# MCU.net
KiCad netlist of a schematic drawn in Altium Designer
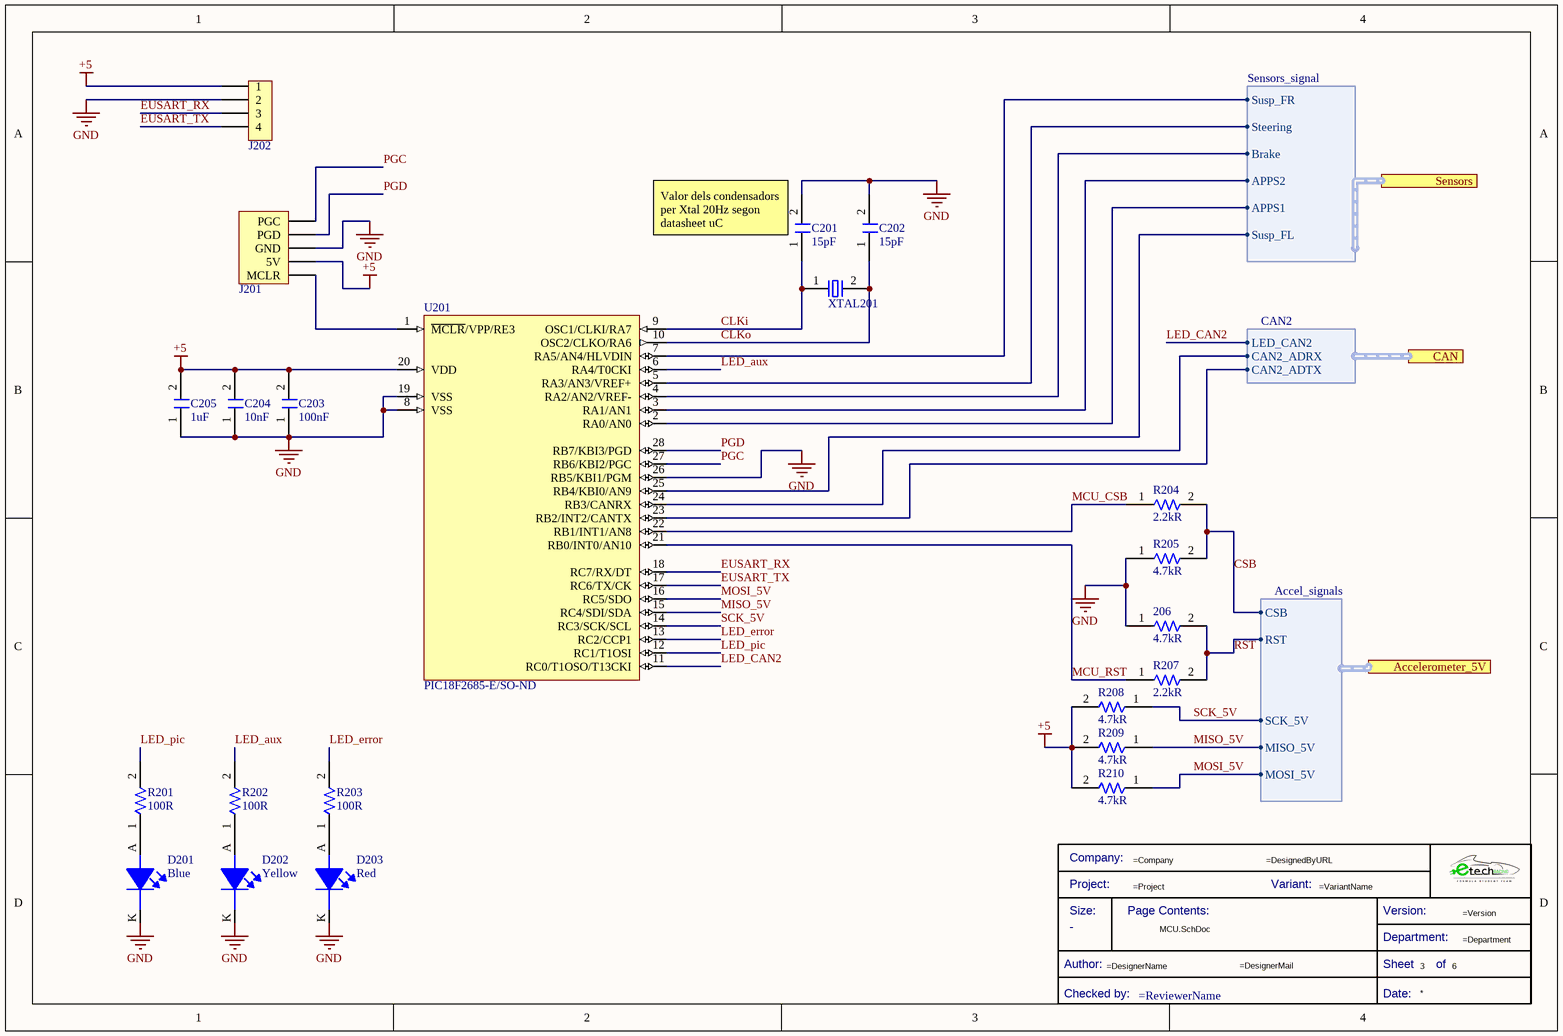
[diagram p0: MCU.SchDoc]

(export (version "E")
  (design (tool "Eeschema 10.0.6"))
  (components
    (comp (ref "*")
      (value "Title Block_template")
      (description "Standard Title Block")
      (fields
        (field (name "SIZE") "-")
        (field (name ".CREATOR") "GP")
        (field (name ".PCBCHECK") "GP")
        (field (name ".SCHCHECK") "GP")
      )
      (libsource (lib "e-Tech_Racing") (part "Title Block_template"))
    )
    (comp (ref "206")
      (value "CRS1206-FX-4701ELF")
      (footprint "R1206FTK-W")
      (description "Res Thick Film 1206 4.7K Ohm 1% 1/2W ±100ppm/°C Molded SMD T/R")
      (fields (field (name "TOLERANCE") "1%") (field (name "RESISTANCE") "4.7kR"))
      (libsource (lib "Passives") (part "R4.7K-1206FTK"))
    )
    (comp (ref "C201")
      (value "885012008038")
      (footprint "C1206FNPC-RW")
      (description "Cap, 15Pf, 50V, 5%, C0G/np0, 1206 Rohs Compliant: Yes")
      (fields
        (field (name "MANUFACTURER") "Wurth Electronics")
        (field (name "TOLERANCE") "5%")
        (field (name "CAPACITANCE") "15pF")
      )
      (libsource (lib "Passives") (part "C15p-50V-1206FNPC-NP0"))
    )
    (comp (ref "C202")
      (value "885012008038")
      (footprint "C1206FNPC-RW")
      (description "Cap, 15Pf, 50V, 5%, C0G/np0, 1206 Rohs Compliant: Yes")
      (fields
        (field (name "MANUFACTURER") "Wurth Electronics")
        (field (name "TOLERANCE") "5%")
        (field (name "CAPACITANCE") "15pF")
      )
      (libsource (lib "Passives") (part "C15p-50V-1206FNPC-NP0"))
    )
    (comp (ref "C203")
      (value "885012208009")
      (footprint "C1206FNPC-RW")
      (description "Cap, 0.1ΜF, 10V, 10%, X7R, 1206")
      (fields (field (name "TOLERANCE") "10%") (field (name "CAPACITANCE") "100nF"))
      (libsource (lib "Passives") (part "C100n-10V-1206FNPC-X7R"))
    )
    (comp (ref "C204")
      (value "885012208009")
      (footprint "C1206FNPC-RW")
      (description "Cap, 0.1ΜF, 10V, 10%, X7R, 1206")
      (fields (field (name "TOLERANCE") "10%") (field (name "CAPACITANCE") "10nF"))
      (libsource (lib "Passives") (part "C100n-10V-1206FNPC-X7R"))
    )
    (comp (ref "C205")
      (value "885012208009")
      (footprint "C1206FNPC-RW")
      (description "Cap, 0.1ΜF, 10V, 10%, X7R, 1206")
      (fields (field (name "TOLERANCE") "10%") (field (name "CAPACITANCE") "1uF"))
      (libsource (lib "Passives") (part "C100n-10V-1206FNPC-X7R"))
    )
    (comp (ref "D201")
      (value "150120BS75000")
      (footprint "LED_1206_WE")
      (description "Led, Blue, 470 Nm, 3.2 V, 30 Ma, 145 Mcd Rohs Compliant: Yes")
      (fields (field (name "MANUFACTURER") "Wurth Electronics") (field (name "COLOR") "Blue"))
      (libsource (lib "Semiconductor") (part "LEDBS-1206-145"))
    )
    (comp (ref "D202")
      (value "150120YS75000")
      (footprint "LED_1206_WE")
      (description "Led, Yellow, 590 Nm, 2 V, 30 Ma, 120 Mcd Rohs Compliant: Yes")
      (fields (field (name "MANUFACTURER") "Wurth Electronics") (field (name "COLOR") "Yellow"))
      (libsource (lib "Semiconductor") (part "LEDYS-1206-120"))
    )
    (comp (ref "D203")
      (value "150120RS75000")
      (footprint "LED_1206_WE")
      (description "Led, Red, 625 Nm, 2 V, 30 Ma, 150 Mcd Rohs Compliant: Yes")
      (fields (field (name "MANUFACTURER") "Wurth Electronics") (field (name "COLOR") "Red"))
      (libsource (lib "Semiconductor") (part "LEDRS-1206-150"))
    )
    (comp (ref "J201")
      (value "61300511121")
      (footprint "J_Bootloader_PIC")
      (description "THT Vertical Pin Header WR-PHD, Pitch 2.54 mm, Single Row, 5 pins")
      (fields (field (name "MANUFACTURER") "Molex"))
      (libsource (lib "Electromechanical") (part "J_Bootloader_PIC_5V"))
    )
    (comp (ref "J202")
      (value "61300411121")
      (footprint "J_PinHeader_1x4")
      (description "CONN HEADER 4 POS 2.54")
      (fields (field (name ".CREATOR") "AC"))
      (libsource (lib "Electromechanical") (part "J_UART"))
    )
    (comp (ref "R201")
      (value "CRG1206F100R")
      (footprint "R1206FTK-W")
      (description "Res Thick Film 1206 100 Ohm 1% 0.25W(1/4W) ±200ppm/C Pad SMD T/R")
      (fields
        (field (name "MANUFACTURER") "TE Connectivity")
        (field (name "TOLERANCE") "1%")
        (field (name "RESISTANCE") "100R")
      )
      (libsource (lib "Passives") (part "R100-1206FTK"))
    )
    (comp (ref "R202")
      (value "CRG1206F100R")
      (footprint "R1206FTK-W")
      (description "Res Thick Film 1206 100 Ohm 1% 0.25W(1/4W) ±200ppm/C Pad SMD T/R")
      (fields
        (field (name "MANUFACTURER") "TE Connectivity")
        (field (name "TOLERANCE") "1%")
        (field (name "RESISTANCE") "100R")
      )
      (libsource (lib "Passives") (part "R100-1206FTK"))
    )
    (comp (ref "R203")
      (value "CRG1206F100R")
      (footprint "R1206FTK-W")
      (description "Res Thick Film 1206 100 Ohm 1% 0.25W(1/4W) ±200ppm/C Pad SMD T/R")
      (fields
        (field (name "MANUFACTURER") "TE Connectivity")
        (field (name "TOLERANCE") "1%")
        (field (name "RESISTANCE") "100R")
      )
      (libsource (lib "Passives") (part "R100-1206FTK"))
    )
    (comp (ref "R204")
      (value "CR1206-FX-2201ELF")
      (footprint "R1206FTK-W")
      (description "Res Thick Film 1206 2.2K Ohm 1% 1/4W ±100ppm/°C Molded SMD SMD Paper Tape on Plastic Reel")
      (fields (field (name "TOLERANCE") "1%") (field (name "RESISTANCE") "2.2kR"))
      (libsource (lib "Passives") (part "R2.2K-1206FTK"))
    )
    (comp (ref "R205")
      (value "CRS1206-FX-4701ELF")
      (footprint "R1206FTK-W")
      (description "Res Thick Film 1206 4.7K Ohm 1% 1/2W ±100ppm/°C Molded SMD T/R")
      (fields (field (name "TOLERANCE") "1%") (field (name "RESISTANCE") "4.7kR"))
      (libsource (lib "Passives") (part "R4.7K-1206FTK"))
    )
    (comp (ref "R207")
      (value "CR1206-FX-2201ELF")
      (footprint "R1206FTK-W")
      (description "Res Thick Film 1206 2.2K Ohm 1% 1/4W ±100ppm/°C Molded SMD SMD Paper Tape on Plastic Reel")
      (fields (field (name "TOLERANCE") "1%") (field (name "RESISTANCE") "2.2kR"))
      (libsource (lib "Passives") (part "R2.2K-1206FTK"))
    )
    (comp (ref "R208")
      (value "CRS1206-FX-4701ELF")
      (footprint "R1206FTK-W")
      (description "Res Thick Film 1206 4.7K Ohm 1% 1/2W ±100ppm/°C Molded SMD T/R")
      (fields (field (name "TOLERANCE") "1%") (field (name "RESISTANCE") "4.7kR"))
      (libsource (lib "Passives") (part "R4.7K-1206FTK"))
    )
    (comp (ref "R209")
      (value "CRS1206-FX-4701ELF")
      (footprint "R1206FTK-W")
      (description "Res Thick Film 1206 4.7K Ohm 1% 1/2W ±100ppm/°C Molded SMD T/R")
      (fields (field (name "TOLERANCE") "1%") (field (name "RESISTANCE") "4.7kR"))
      (libsource (lib "Passives") (part "R4.7K-1206FTK"))
    )
    (comp (ref "R210")
      (value "CRS1206-FX-4701ELF")
      (footprint "R1206FTK-W")
      (description "Res Thick Film 1206 4.7K Ohm 1% 1/2W ±100ppm/°C Molded SMD T/R")
      (fields (field (name "TOLERANCE") "1%") (field (name "RESISTANCE") "4.7kR"))
      (libsource (lib "Passives") (part "R4.7K-1206FTK"))
    )
    (comp (ref "U201")
      (value "PIC18F2685")
      (footprint "U_PIC18F2685")
      (description "PIC18F2685-E/SO; 8bit PIC Microcontroller; 40MHz; 96kb; 1024 B Flash; 28-Pin SOIC")
      (fields (field (name "SUPPLIER PART NUMBER 1") "PIC18F2685-E/SO-ND"))
      (libsource (lib "Integrated circuits") (part "U_PIC18F2685"))
    )
    (comp (ref "XTAL201")
      (value "830028710")
      (footprint "XTAL20M_SMD")
      (description "830028710, 20 MHz")
      (fields (field (name "MANUFACTURER") "Würth Elektronik"))
      (libsource (lib "Passives") (part "XTAL20M_SMD"))
    )
  )
  (nets
    (net (code "4") (name "+5") (class "Default")
      (node (ref "C203") (pin "2") (pinfunction "2_2") (pintype "passive"))
      (node (ref "C204") (pin "2") (pinfunction "2_2") (pintype "passive"))
      (node (ref "C205") (pin "2") (pinfunction "2_2") (pintype "passive"))
      (node (ref "J201") (pin "2") (pinfunction "5V_2") (pintype "passive"))
      (node (ref "J202") (pin "1") (pinfunction "1_1") (pintype "passive"))
      (node (ref "R208") (pin "2") (pinfunction "2_2") (pintype "passive"))
      (node (ref "R209") (pin "2") (pinfunction "2_2") (pintype "passive"))
      (node (ref "R210") (pin "2") (pinfunction "2_2") (pintype "passive"))
      (node (ref "U201") (pin "20") (pinfunction "VDD_20") (pintype "input"))
    )
    (net (code "5") (name "/APPS1") (class "Default")
      (node (ref "U201") (pin "2") (pinfunction "RA0/AN0_2") (pintype "bidirectional"))
    )
    (net (code "6") (name "/APPS2") (class "Default")
      (node (ref "U201") (pin "3") (pinfunction "RA1/AN1_3") (pintype "bidirectional"))
    )
    (net (code "7") (name "/Brake") (class "Default")
      (node (ref "U201") (pin "4") (pinfunction "RA2/AN2/VREF-_4") (pintype "bidirectional"))
    )
    (net (code "8") (name "/CAN2_ADRX") (class "Default")
      (node (ref "U201") (pin "24") (pinfunction "RB3/CANRX_24") (pintype "bidirectional"))
    )
    (net (code "9") (name "/CAN2_ADTX") (class "Default")
      (node (ref "U201") (pin "23") (pinfunction "RB2/INT2/CANTX_23") (pintype "bidirectional"))
    )
    (net (code "10") (name "/CLKi") (class "Default")
      (node (ref "C201") (pin "1") (pinfunction "1_1") (pintype "passive"))
      (node (ref "U201") (pin "9") (pinfunction "OSC1/CLKI/RA7_9") (pintype "input"))
      (node (ref "XTAL201") (pin "1") (pinfunction "1_1") (pintype "passive"))
    )
    (net (code "11") (name "/CLKo") (class "Default")
      (node (ref "C202") (pin "1") (pinfunction "1_1") (pintype "passive"))
      (node (ref "U201") (pin "10") (pinfunction "OSC2/CLKO/RA6_10") (pintype "output"))
      (node (ref "XTAL201") (pin "2") (pinfunction "2_2") (pintype "passive"))
    )
    (net (code "12") (name "/CSB") (class "Default")
      (node (ref "R204") (pin "2") (pinfunction "2_2") (pintype "passive"))
      (node (ref "R205") (pin "2") (pinfunction "2_2") (pintype "passive"))
    )
    (net (code "13") (name "/EUSART_RX") (class "Default")
      (node (ref "J202") (pin "3") (pinfunction "3_3") (pintype "passive"))
      (node (ref "U201") (pin "18") (pinfunction "RC7/RX/DT_18") (pintype "bidirectional"))
    )
    (net (code "14") (name "/EUSART_TX") (class "Default")
      (node (ref "J202") (pin "4") (pinfunction "4_4") (pintype "passive"))
      (node (ref "U201") (pin "17") (pinfunction "RC6/TX/CK_17") (pintype "bidirectional"))
    )
    (net (code "15") (name "/LED_CAN2") (class "Default")
      (node (ref "U201") (pin "11") (pinfunction "RC0/T1OSO/T13CKI_11") (pintype "bidirectional"))
    )
    (net (code "16") (name "/LED_aux") (class "Default")
      (node (ref "R202") (pin "2") (pinfunction "2_2") (pintype "passive"))
      (node (ref "U201") (pin "6") (pinfunction "RA4/T0CKI_6") (pintype "bidirectional"))
    )
    (net (code "17") (name "/LED_error") (class "Default")
      (node (ref "R203") (pin "2") (pinfunction "2_2") (pintype "passive"))
      (node (ref "U201") (pin "13") (pinfunction "RC2/CCP1_13") (pintype "bidirectional"))
    )
    (net (code "18") (name "/LED_pic") (class "Default")
      (node (ref "R201") (pin "2") (pinfunction "2_2") (pintype "passive"))
      (node (ref "U201") (pin "12") (pinfunction "RC1/T1OSI_12") (pintype "bidirectional"))
    )
    (net (code "19") (name "/MCU_CSB") (class "Default")
      (node (ref "R204") (pin "1") (pinfunction "1_1") (pintype "passive"))
      (node (ref "U201") (pin "22") (pinfunction "RB1/INT1/AN8_22") (pintype "bidirectional"))
    )
    (net (code "20") (name "/MCU_RST") (class "Default")
      (node (ref "R207") (pin "1") (pinfunction "1_1") (pintype "passive"))
      (node (ref "U201") (pin "21") (pinfunction "RB0/INT0/AN10_21") (pintype "bidirectional"))
    )
    (net (code "21") (name "/MISO_5V") (class "Default")
      (node (ref "R209") (pin "1") (pinfunction "1_1") (pintype "passive"))
      (node (ref "U201") (pin "15") (pinfunction "RC4/SDI/SDA_15") (pintype "bidirectional"))
    )
    (net (code "22") (name "/MOSI_5V") (class "Default")
      (node (ref "R210") (pin "1") (pinfunction "1_1") (pintype "passive"))
      (node (ref "U201") (pin "16") (pinfunction "RC5/SDO_16") (pintype "bidirectional"))
    )
    (net (code "23") (name "/PGC") (class "Default")
      (node (ref "J201") (pin "5") (pinfunction "PGC_5") (pintype "passive"))
      (node (ref "U201") (pin "27") (pinfunction "RB6/KBI2/PGC_27") (pintype "bidirectional"))
    )
    (net (code "24") (name "/PGD") (class "Default")
      (node (ref "J201") (pin "4") (pinfunction "PGD_4") (pintype "passive"))
      (node (ref "U201") (pin "28") (pinfunction "RB7/KBI3/PGD_28") (pintype "bidirectional"))
    )
    (net (code "25") (name "/RST") (class "Default")
      (node (ref "206") (pin "2") (pinfunction "2_2") (pintype "passive"))
      (node (ref "R207") (pin "2") (pinfunction "2_2") (pintype "passive"))
    )
    (net (code "26") (name "/SCK_5V") (class "Default")
      (node (ref "R208") (pin "1") (pinfunction "1_1") (pintype "passive"))
      (node (ref "U201") (pin "14") (pinfunction "RC3/SCK/SCL_14") (pintype "bidirectional"))
    )
    (net (code "27") (name "/Steering") (class "Default")
      (node (ref "U201") (pin "5") (pinfunction "RA3/AN3/VREF+_5") (pintype "bidirectional"))
    )
    (net (code "28") (name "/Susp_FL") (class "Default")
      (node (ref "U201") (pin "25") (pinfunction "RB4/KBI0/AN9_25") (pintype "bidirectional"))
    )
    (net (code "29") (name "/Susp_FR") (class "Default")
      (node (ref "U201") (pin "7") (pinfunction "RA5/AN4/HLVDIN_7") (pintype "bidirectional"))
    )
    (net (code "33") (name "GND") (class "Default")
      (node (ref "206") (pin "1") (pinfunction "1_1") (pintype "passive"))
      (node (ref "C201") (pin "2") (pinfunction "2_2") (pintype "passive"))
      (node (ref "C202") (pin "2") (pinfunction "2_2") (pintype "passive"))
      (node (ref "C203") (pin "1") (pinfunction "1_1") (pintype "passive"))
      (node (ref "C204") (pin "1") (pinfunction "1_1") (pintype "passive"))
      (node (ref "C205") (pin "1") (pinfunction "1_1") (pintype "passive"))
      (node (ref "D201") (pin "K") (pinfunction "K_K") (pintype "passive"))
      (node (ref "D202") (pin "K") (pinfunction "K_K") (pintype "passive"))
      (node (ref "D203") (pin "K") (pinfunction "K_K") (pintype "passive"))
      (node (ref "J201") (pin "3") (pinfunction "GND_3") (pintype "passive"))
      (node (ref "J202") (pin "2") (pinfunction "2_2") (pintype "passive"))
      (node (ref "R205") (pin "1") (pinfunction "1_1") (pintype "passive"))
      (node (ref "U201") (pin "19") (pinfunction "VSS_19") (pintype "input"))
      (node (ref "U201") (pin "26") (pinfunction "RB5/KBI1/PGM_26") (pintype "bidirectional"))
      (node (ref "U201") (pin "8") (pinfunction "VSS_8") (pintype "input"))
    )
    (net (code "34") (name "Net-(D201-PadA)") (class "Default")
      (node (ref "D201") (pin "A") (pinfunction "A_A") (pintype "passive"))
      (node (ref "R201") (pin "1") (pinfunction "1_1") (pintype "passive"))
    )
    (net (code "35") (name "Net-(D202-PadA)") (class "Default")
      (node (ref "D202") (pin "A") (pinfunction "A_A") (pintype "passive"))
      (node (ref "R202") (pin "1") (pinfunction "1_1") (pintype "passive"))
    )
    (net (code "36") (name "Net-(D203-PadA)") (class "Default")
      (node (ref "D203") (pin "A") (pinfunction "A_A") (pintype "passive"))
      (node (ref "R203") (pin "1") (pinfunction "1_1") (pintype "passive"))
    )
    (net (code "37") (name "Net-(J201-MCLR)") (class "Default")
      (node (ref "J201") (pin "1") (pinfunction "MCLR_1") (pintype "passive"))
      (node (ref "U201") (pin "1") (pinfunction "~{MCLR}/VPP/RE3_1") (pintype "input"))
    )
  )
)
